# buckconverter.net
KiCad netlist of a schematic drawn in EAGLE
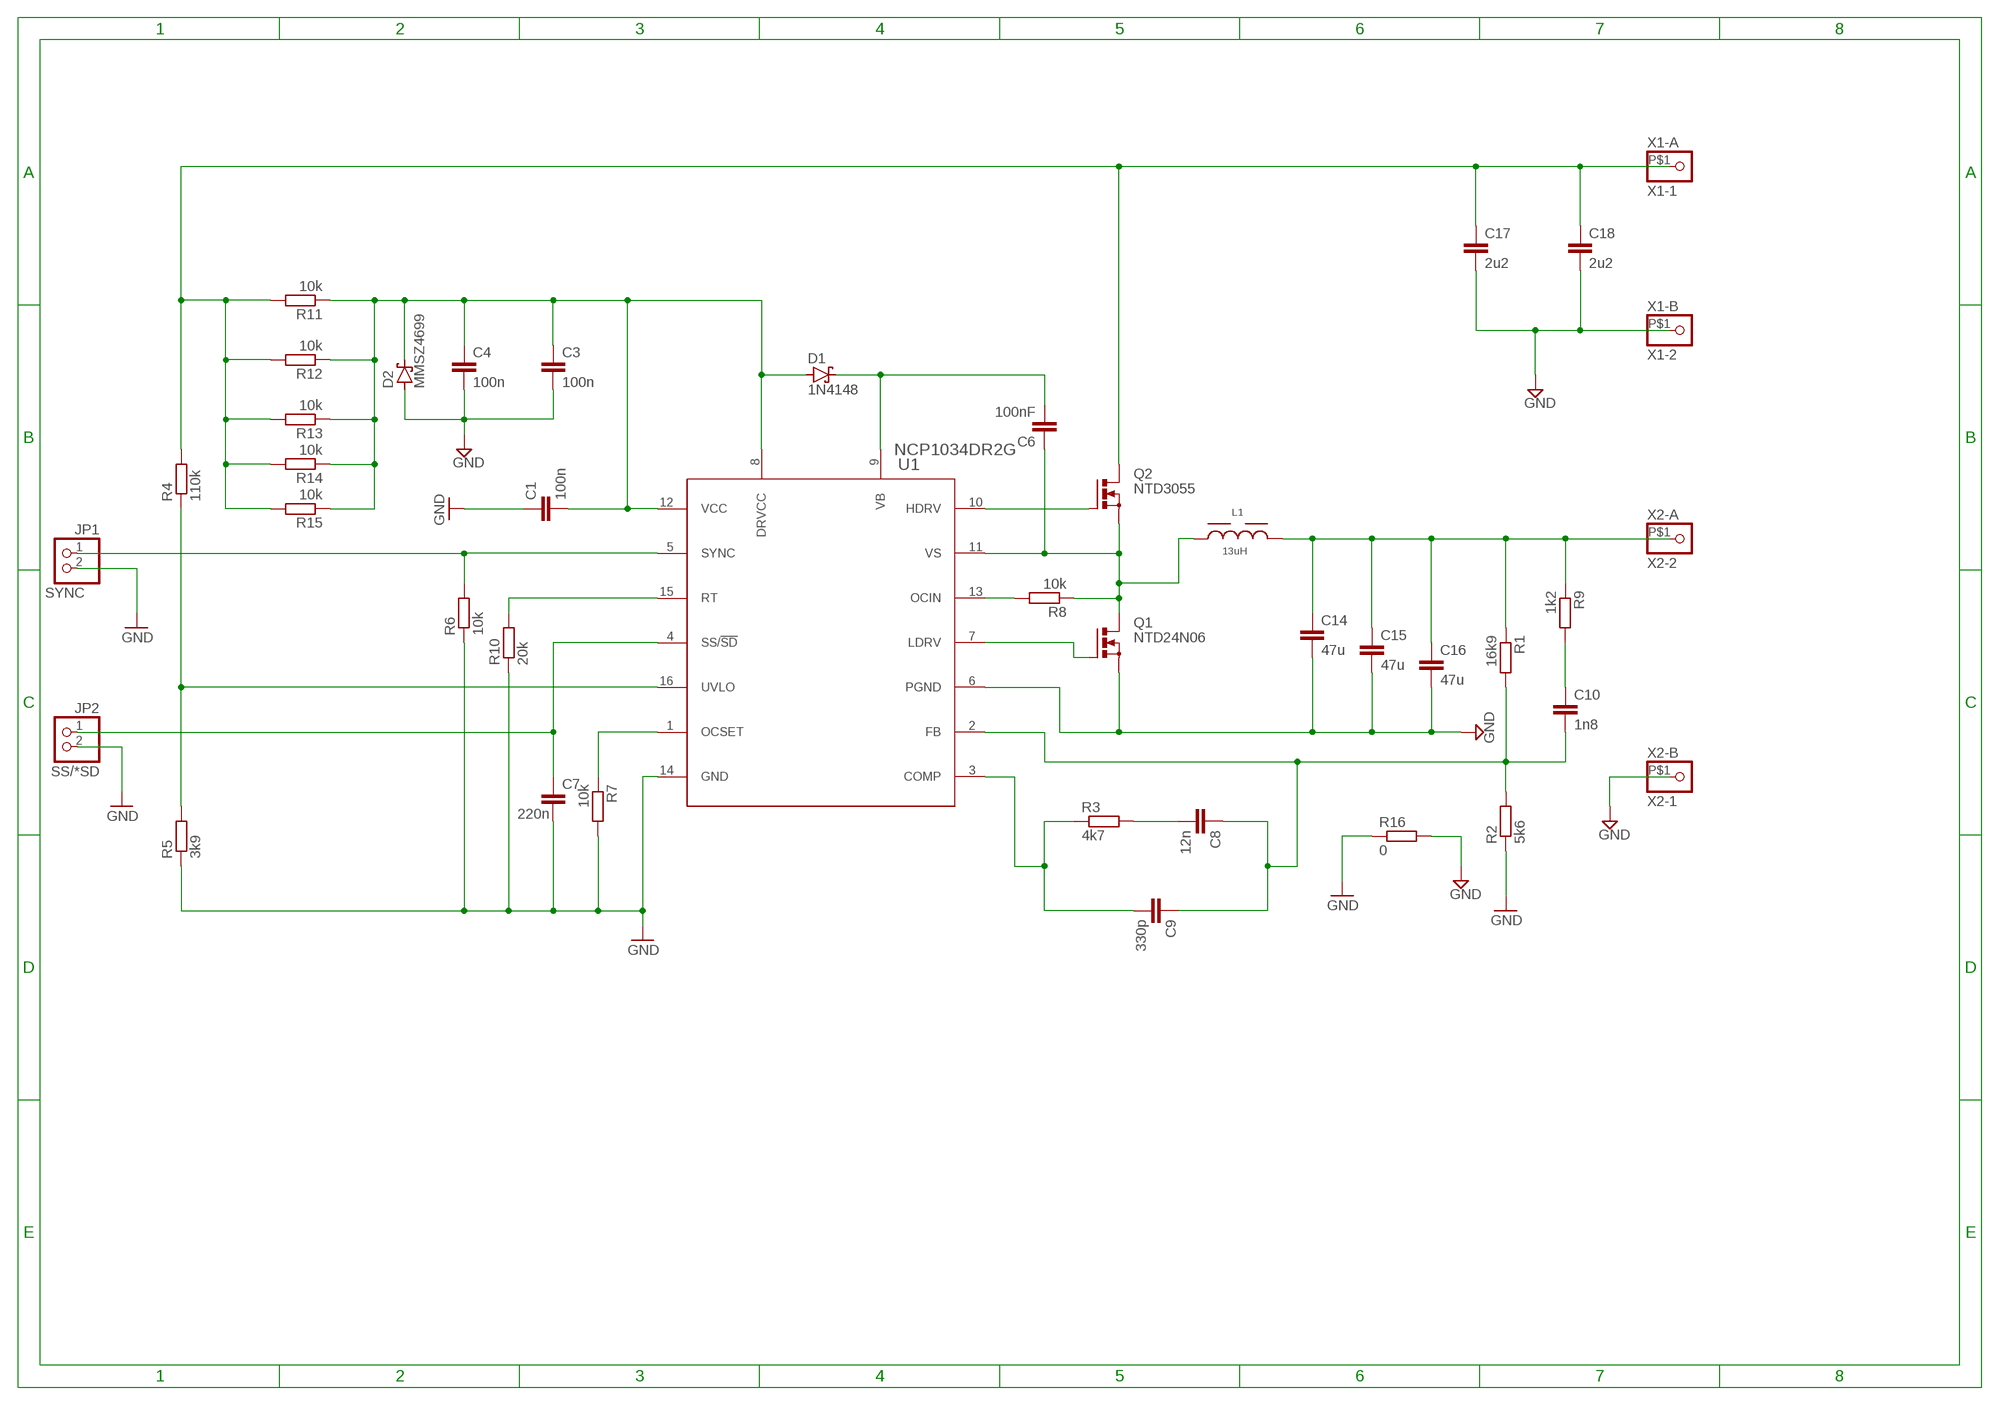
[diagram p0: schematic, sheet 1]

(export (version "E")
  (design (tool "Eeschema 10.0.6"))
  (components
    (comp (ref "C1")
      (value "100n")
      (footprint "eagle-import:C1206")
      (libsource (lib "eagle-import") (part "C-EUC1206"))
    )
    (comp (ref "C3")
      (value "100n")
      (footprint "eagle-import:C1206")
      (libsource (lib "eagle-import") (part "C-EUC1206"))
    )
    (comp (ref "C4")
      (value "100n")
      (footprint "eagle-import:C1206")
      (libsource (lib "eagle-import") (part "C-EUC1206"))
    )
    (comp (ref "C6")
      (value "100nF")
      (footprint "eagle-import:C1206")
      (libsource (lib "eagle-import") (part "C-EUC1206"))
    )
    (comp (ref "C7")
      (value "220n")
      (footprint "eagle-import:C1206")
      (libsource (lib "eagle-import") (part "C-EUC1206"))
    )
    (comp (ref "C8")
      (value "12n")
      (footprint "eagle-import:C1206")
      (libsource (lib "eagle-import") (part "C-EUC1206"))
    )
    (comp (ref "C9")
      (value "330p")
      (footprint "eagle-import:C1206")
      (libsource (lib "eagle-import") (part "C-EUC1206"))
    )
    (comp (ref "C10")
      (value "1n8")
      (footprint "eagle-import:C1206")
      (libsource (lib "eagle-import") (part "C-EUC1206"))
    )
    (comp (ref "C14")
      (value "47u")
      (footprint "eagle-import:C1210")
      (libsource (lib "eagle-import") (part "C-EUC1210"))
    )
    (comp (ref "C15")
      (value "47u")
      (footprint "eagle-import:C1210")
      (libsource (lib "eagle-import") (part "C-EUC1210"))
    )
    (comp (ref "C16")
      (value "47u")
      (footprint "eagle-import:C1210")
      (libsource (lib "eagle-import") (part "C-EUC1210"))
    )
    (comp (ref "C17")
      (value "2u2")
      (footprint "eagle-import:C1210")
      (libsource (lib "eagle-import") (part "C-EUC1210"))
    )
    (comp (ref "C18")
      (value "2u2")
      (footprint "eagle-import:C1210")
      (libsource (lib "eagle-import") (part "C-EUC1210"))
    )
    (comp (ref "D1")
      (value "1N4148")
      (footprint "eagle-import:SOT23")
      (libsource (lib "eagle-import") (part "BAS40"))
    )
    (comp (ref "D2")
      (value "MMSZ4699")
      (footprint "eagle-import:SOT23")
      (libsource (lib "eagle-import") (part "BAS40"))
    )
    (comp (ref "JP1")
      (value "SYNC")
      (footprint "eagle-import:1X02")
      (libsource (lib "eagle-import") (part "PINHD-1X2"))
    )
    (comp (ref "JP2")
      (value "SS/*SD")
      (footprint "eagle-import:1X02")
      (libsource (lib "eagle-import") (part "PINHD-1X2"))
    )
    (comp (ref "L1")
      (value "13uH")
      (footprint "eagle-import:WE-HCI_1365")
      (libsource (lib "eagle-import") (part "WE-HCI_1365_7443551131"))
    )
    (comp (ref "Q1")
      (value "NTD24N06")
      (footprint "eagle-import:TO220BV")
      (libsource (lib "eagle-import") (part "PMOSFET_NTO220BV"))
    )
    (comp (ref "Q2")
      (value "NTD3055")
      (footprint "eagle-import:TO220BV")
      (libsource (lib "eagle-import") (part "PMOSFET_NTO220BV"))
    )
    (comp (ref "R1")
      (value "16k9")
      (footprint "eagle-import:R1206")
      (libsource (lib "eagle-import") (part "R-EU_R1206"))
    )
    (comp (ref "R2")
      (value "5k6")
      (footprint "eagle-import:R1206")
      (libsource (lib "eagle-import") (part "R-EU_R1206"))
    )
    (comp (ref "R3")
      (value "4k7")
      (footprint "eagle-import:R1206")
      (libsource (lib "eagle-import") (part "R-EU_R1206"))
    )
    (comp (ref "R4")
      (value "110k")
      (footprint "eagle-import:R1206")
      (libsource (lib "eagle-import") (part "R-EU_R1206"))
    )
    (comp (ref "R5")
      (value "3k9")
      (footprint "eagle-import:R1206")
      (libsource (lib "eagle-import") (part "R-EU_R1206"))
    )
    (comp (ref "R6")
      (value "10k")
      (footprint "eagle-import:R1206")
      (libsource (lib "eagle-import") (part "R-EU_R1206"))
    )
    (comp (ref "R7")
      (value "10k")
      (footprint "eagle-import:R1206")
      (libsource (lib "eagle-import") (part "R-EU_R1206"))
    )
    (comp (ref "R8")
      (value "10k")
      (footprint "eagle-import:R1206")
      (libsource (lib "eagle-import") (part "R-EU_R1206"))
    )
    (comp (ref "R9")
      (value "1k2")
      (footprint "eagle-import:R1206")
      (libsource (lib "eagle-import") (part "R-EU_R1206"))
    )
    (comp (ref "R10")
      (value "20k")
      (footprint "eagle-import:R1206")
      (libsource (lib "eagle-import") (part "R-EU_R1206"))
    )
    (comp (ref "R11")
      (value "10k")
      (footprint "eagle-import:R1206")
      (libsource (lib "eagle-import") (part "R-EU_R1206"))
    )
    (comp (ref "R12")
      (value "10k")
      (footprint "eagle-import:R1206")
      (libsource (lib "eagle-import") (part "R-EU_R1206"))
    )
    (comp (ref "R13")
      (value "10k")
      (footprint "eagle-import:R1206")
      (libsource (lib "eagle-import") (part "R-EU_R1206"))
    )
    (comp (ref "R14")
      (value "10k")
      (footprint "eagle-import:R1206")
      (libsource (lib "eagle-import") (part "R-EU_R1206"))
    )
    (comp (ref "R15")
      (value "10k")
      (footprint "eagle-import:R1206")
      (libsource (lib "eagle-import") (part "R-EU_R1206"))
    )
    (comp (ref "R16")
      (value "0")
      (footprint "eagle-import:R1206")
      (libsource (lib "eagle-import") (part "R-EU_R1206"))
    )
    (comp (ref "U1")
      (value "NCP1034DR2G")
      (footprint "eagle-import:SOIC-16_ONS")
      (fields (field (name "COPYRIGHT") "Copyright (C) 2022 Ultra Librarian. All rights reserved."))
      (libsource (lib "eagle-import") (part "NCP1034DR2G"))
    )
    (comp (ref "X1-A")
      (value "X1-1")
      (footprint "eagle-import:1X1-BIGPOGO")
      (libsource (lib "eagle-import") (part "PINHD-1X1-BIGPOGO"))
    )
    (comp (ref "X1-B")
      (value "X1-2")
      (footprint "eagle-import:1X1-BIGPOGO")
      (libsource (lib "eagle-import") (part "PINHD-1X1-BIGPOGO"))
    )
    (comp (ref "X2-A")
      (value "X2-2")
      (footprint "eagle-import:1X1-BIGPOGO")
      (libsource (lib "eagle-import") (part "PINHD-1X1-BIGPOGO"))
    )
    (comp (ref "X2-B")
      (value "X2-1")
      (footprint "eagle-import:1X1-BIGPOGO")
      (libsource (lib "eagle-import") (part "PINHD-1X1-BIGPOGO"))
    )
  )
  (nets
    (net (code "1") (name "GND") (class "Default")
      (node (ref "C1") (pin "1") (pinfunction "1_1") (pintype "passive"))
      (node (ref "C14") (pin "2") (pinfunction "2_2") (pintype "passive"))
      (node (ref "C15") (pin "2") (pinfunction "2_2") (pintype "passive"))
      (node (ref "C16") (pin "2") (pinfunction "2_2") (pintype "passive"))
      (node (ref "C17") (pin "2") (pinfunction "2_2") (pintype "passive"))
      (node (ref "C18") (pin "2") (pinfunction "2_2") (pintype "passive"))
      (node (ref "C3") (pin "2") (pinfunction "2_2") (pintype "passive"))
      (node (ref "C4") (pin "2") (pinfunction "2_2") (pintype "passive"))
      (node (ref "C7") (pin "2") (pinfunction "2_2") (pintype "passive"))
      (node (ref "D2") (pin "1") (pinfunction "A_1") (pintype "passive"))
      (node (ref "JP1") (pin "2") (pinfunction "2_2") (pintype "passive"))
      (node (ref "JP2") (pin "2") (pinfunction "2_2") (pintype "passive"))
      (node (ref "Q1") (pin "S") (pinfunction "S_S") (pintype "passive"))
      (node (ref "R10") (pin "1") (pinfunction "1_1") (pintype "passive"))
      (node (ref "R16") (pin "1") (pinfunction "1_1") (pintype "passive"))
      (node (ref "R16") (pin "2") (pinfunction "2_2") (pintype "passive"))
      (node (ref "R2") (pin "1") (pinfunction "1_1") (pintype "passive"))
      (node (ref "R5") (pin "1") (pinfunction "1_1") (pintype "passive"))
      (node (ref "R6") (pin "1") (pinfunction "1_1") (pintype "passive"))
      (node (ref "R7") (pin "2") (pinfunction "2_2") (pintype "passive"))
      (node (ref "U1") (pin "14") (pinfunction "GND_14") (pintype "power_in"))
      (node (ref "U1") (pin "6") (pinfunction "PGND_6") (pintype "power_in"))
      (node (ref "X1-B") (pin "P$1") (pinfunction "1_P$1") (pintype "passive"))
      (node (ref "X2-B") (pin "P$1") (pinfunction "1_P$1") (pintype "passive"))
    )
    (net (code "2") (name "Net-(C8-Pad2)") (class "Default")
      (node (ref "C8") (pin "2") (pinfunction "2_2") (pintype "passive"))
      (node (ref "R3") (pin "2") (pinfunction "2_2") (pintype "passive"))
    )
    (net (code "3") (name "Net-(C10-Pad1)") (class "Default")
      (node (ref "C10") (pin "1") (pinfunction "1_1") (pintype "passive"))
      (node (ref "R9") (pin "2") (pinfunction "2_2") (pintype "passive"))
    )
    (net (code "4") (name "Net-(D1-A)") (class "Default")
      (node (ref "C1") (pin "2") (pinfunction "2_2") (pintype "passive"))
      (node (ref "C3") (pin "1") (pinfunction "1_1") (pintype "passive"))
      (node (ref "C4") (pin "1") (pinfunction "1_1") (pintype "passive"))
      (node (ref "D1") (pin "1") (pinfunction "A_1") (pintype "passive"))
      (node (ref "D2") (pin "3") (pinfunction "C_3") (pintype "passive"))
      (node (ref "R11") (pin "1") (pinfunction "1_1") (pintype "passive"))
      (node (ref "R12") (pin "1") (pinfunction "1_1") (pintype "passive"))
      (node (ref "R13") (pin "1") (pinfunction "1_1") (pintype "passive"))
      (node (ref "R14") (pin "1") (pinfunction "1_1") (pintype "passive"))
      (node (ref "R15") (pin "1") (pinfunction "1_1") (pintype "passive"))
      (node (ref "U1") (pin "12") (pinfunction "VCC_12") (pintype "power_in"))
      (node (ref "U1") (pin "8") (pinfunction "DRVCC_8") (pintype "passive"))
    )
    (net (code "5") (name "Net-(D1-C)") (class "Default")
      (node (ref "C6") (pin "2") (pinfunction "2_2") (pintype "passive"))
      (node (ref "D1") (pin "3") (pinfunction "C_3") (pintype "passive"))
      (node (ref "U1") (pin "9") (pinfunction "VB_9") (pintype "passive"))
    )
    (net (code "6") (name "Net-(U1-COMP)") (class "Default")
      (node (ref "C9") (pin "2") (pinfunction "2_2") (pintype "passive"))
      (node (ref "R3") (pin "1") (pinfunction "1_1") (pintype "passive"))
      (node (ref "U1") (pin "3") (pinfunction "COMP_3") (pintype "output"))
    )
    (net (code "7") (name "Net-(U1-FB)") (class "Default")
      (node (ref "C10") (pin "2") (pinfunction "2_2") (pintype "passive"))
      (node (ref "C8") (pin "1") (pinfunction "1_1") (pintype "passive"))
      (node (ref "C9") (pin "1") (pinfunction "1_1") (pintype "passive"))
      (node (ref "R1") (pin "2") (pinfunction "2_2") (pintype "passive"))
      (node (ref "R2") (pin "2") (pinfunction "2_2") (pintype "passive"))
      (node (ref "U1") (pin "2") (pinfunction "FB_2") (pintype "input"))
    )
    (net (code "8") (name "Net-(U1-HDRV)") (class "Default")
      (node (ref "Q2") (pin "G") (pinfunction "G_G") (pintype "passive"))
      (node (ref "U1") (pin "10") (pinfunction "HDRV_10") (pintype "output"))
    )
    (net (code "9") (name "Net-(U1-LDRV)") (class "Default")
      (node (ref "Q1") (pin "G") (pinfunction "G_G") (pintype "passive"))
      (node (ref "U1") (pin "7") (pinfunction "LDRV_7") (pintype "output"))
    )
    (net (code "10") (name "Net-(U1-OCIN)") (class "Default")
      (node (ref "R8") (pin "2") (pinfunction "2_2") (pintype "passive"))
      (node (ref "U1") (pin "13") (pinfunction "OCIN_13") (pintype "input"))
    )
    (net (code "11") (name "Net-(U1-OCSET)") (class "Default")
      (node (ref "R7") (pin "1") (pinfunction "1_1") (pintype "passive"))
      (node (ref "U1") (pin "1") (pinfunction "OCSET_1") (pintype "passive"))
    )
    (net (code "12") (name "Net-(U1-RT)") (class "Default")
      (node (ref "R10") (pin "2") (pinfunction "2_2") (pintype "passive"))
      (node (ref "U1") (pin "15") (pinfunction "RT_15") (pintype "passive"))
    )
    (net (code "13") (name "Net-(U1-SS{slash}~{SD})") (class "Default")
      (node (ref "C7") (pin "1") (pinfunction "1_1") (pintype "passive"))
      (node (ref "JP2") (pin "1") (pinfunction "1_1") (pintype "passive"))
      (node (ref "U1") (pin "4") (pinfunction "SS/~{SD}_4") (pintype "passive"))
    )
    (net (code "14") (name "Net-(U1-SYNC)") (class "Default")
      (node (ref "JP1") (pin "1") (pinfunction "1_1") (pintype "passive"))
      (node (ref "R6") (pin "2") (pinfunction "2_2") (pintype "passive"))
      (node (ref "U1") (pin "5") (pinfunction "SYNC_5") (pintype "passive"))
    )
    (net (code "15") (name "Net-(U1-UVLO)") (class "Default")
      (node (ref "R4") (pin "1") (pinfunction "1_1") (pintype "passive"))
      (node (ref "R5") (pin "2") (pinfunction "2_2") (pintype "passive"))
      (node (ref "U1") (pin "16") (pinfunction "UVLO_16") (pintype "passive"))
    )
    (net (code "16") (name "Net-(U1-VS)") (class "Default")
      (node (ref "C6") (pin "1") (pinfunction "1_1") (pintype "passive"))
      (node (ref "L1") (pin "1") (pinfunction "1_1") (pintype "passive"))
      (node (ref "Q1") (pin "D") (pinfunction "D_D") (pintype "passive"))
      (node (ref "Q2") (pin "S") (pinfunction "S_S") (pintype "passive"))
      (node (ref "R8") (pin "1") (pinfunction "1_1") (pintype "passive"))
      (node (ref "U1") (pin "11") (pinfunction "VS_11") (pintype "passive"))
    )
    (net (code "17") (name "Net-(X1-A-1)") (class "Default")
      (node (ref "C17") (pin "1") (pinfunction "1_1") (pintype "passive"))
      (node (ref "C18") (pin "1") (pinfunction "1_1") (pintype "passive"))
      (node (ref "Q2") (pin "D") (pinfunction "D_D") (pintype "passive"))
      (node (ref "R11") (pin "2") (pinfunction "2_2") (pintype "passive"))
      (node (ref "R12") (pin "2") (pinfunction "2_2") (pintype "passive"))
      (node (ref "R13") (pin "2") (pinfunction "2_2") (pintype "passive"))
      (node (ref "R14") (pin "2") (pinfunction "2_2") (pintype "passive"))
      (node (ref "R15") (pin "2") (pinfunction "2_2") (pintype "passive"))
      (node (ref "R4") (pin "2") (pinfunction "2_2") (pintype "passive"))
      (node (ref "X1-A") (pin "P$1") (pinfunction "1_P$1") (pintype "passive"))
    )
    (net (code "18") (name "Net-(X2-A-1)") (class "Default")
      (node (ref "C14") (pin "1") (pinfunction "1_1") (pintype "passive"))
      (node (ref "C15") (pin "1") (pinfunction "1_1") (pintype "passive"))
      (node (ref "C16") (pin "1") (pinfunction "1_1") (pintype "passive"))
      (node (ref "L1") (pin "2") (pinfunction "2_2") (pintype "passive"))
      (node (ref "R1") (pin "1") (pinfunction "1_1") (pintype "passive"))
      (node (ref "R9") (pin "1") (pinfunction "1_1") (pintype "passive"))
      (node (ref "X2-A") (pin "P$1") (pinfunction "1_P$1") (pintype "passive"))
    )
  )
)
